# untitled.net
KiCad netlist of a schematic drawn in EAGLE
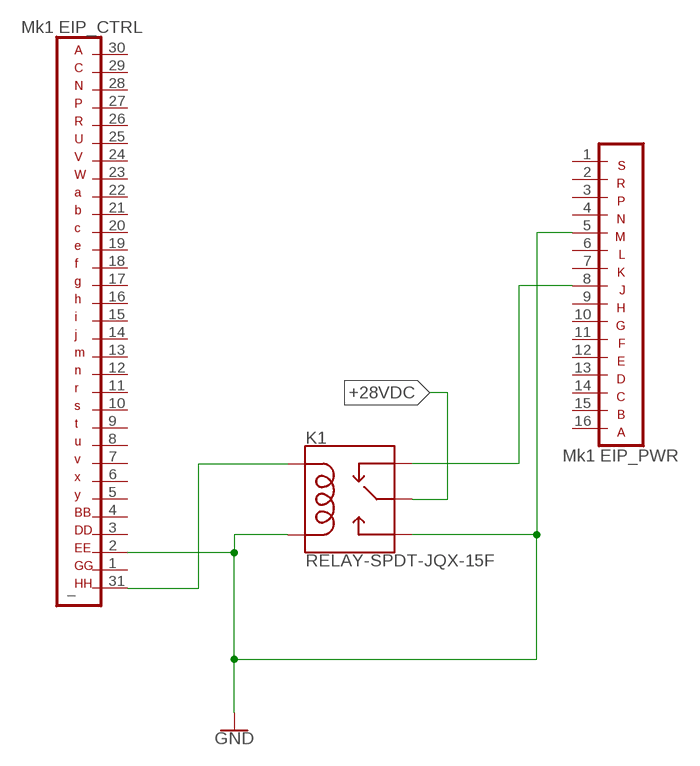
[diagram p0: schematic, sheet 1]

(export (version "E")
  (design (tool "Eeschema 10.0.6"))
  (components
    (comp (ref "J2")
      (value "SDGDSGG")
      (footprint "eagle-import:1X30")
      (libsource (lib "eagle-import") (part "SDGDSGG"))
    )
    (comp (ref "K1")
      (value "RELAY-SPDT-JQX-15F")
      (footprint "eagle-import:RELAY-T90")
      (libsource (lib "eagle-import") (part "RELAY-SPDT-JQX-15F"))
    )
    (comp (ref "U$1")
      (value "MK1_EIP_PWR")
      (footprint "eagle-import:1X16")
      (libsource (lib "eagle-import") (part "MK1_EIP_PWR"))
    )
  )
  (nets
    (net (code "1") (name "+28VDC") (class "Default")
      (node (ref "K1") (pin "MAIN") (pinfunction "MAIN_MAIN") (pintype "bidirectional"))
    )
    (net (code "2") (name "GND") (class "Default")
      (node (ref "J2") (pin "2") (pinfunction "2_2") (pintype "passive"))
      (node (ref "K1") (pin "COIL2") (pinfunction "COIL2_COIL2") (pintype "bidirectional"))
      (node (ref "K1") (pin "NO") (pinfunction "NO_NO") (pintype "bidirectional"))
      (node (ref "U$1") (pin "5") (pinfunction "5_5") (pintype "passive"))
    )
    (net (code "3") (name "Net-(J2-_)") (class "Default")
      (node (ref "J2") (pin "31") (pinfunction "__31") (pintype "passive"))
      (node (ref "K1") (pin "COIL1") (pinfunction "COIL1_COIL1") (pintype "bidirectional"))
    )
    (net (code "4") (name "Net-(K1-PadNC)") (class "Default")
      (node (ref "K1") (pin "NC") (pinfunction "NC_NC") (pintype "bidirectional"))
      (node (ref "U$1") (pin "8") (pinfunction "8_8") (pintype "passive"))
    )
    (net (code "5") (name "unconnected-(J2-Pad1)") (class "Default")
      (node (ref "J2") (pin "1") (pinfunction "1_1") (pintype "passive"))
    )
    (net (code "6") (name "unconnected-(J2-Pad3)") (class "Default")
      (node (ref "J2") (pin "3") (pinfunction "3_3") (pintype "passive"))
    )
    (net (code "7") (name "unconnected-(J2-Pad4)") (class "Default")
      (node (ref "J2") (pin "4") (pinfunction "4_4") (pintype "passive"))
    )
    (net (code "8") (name "unconnected-(J2-Pad5)") (class "Default")
      (node (ref "J2") (pin "5") (pinfunction "5_5") (pintype "passive"))
    )
    (net (code "9") (name "unconnected-(J2-Pad6)") (class "Default")
      (node (ref "J2") (pin "6") (pinfunction "6_6") (pintype "passive"))
    )
    (net (code "10") (name "unconnected-(J2-Pad7)") (class "Default")
      (node (ref "J2") (pin "7") (pinfunction "7_7") (pintype "passive"))
    )
    (net (code "11") (name "unconnected-(J2-Pad8)") (class "Default")
      (node (ref "J2") (pin "8") (pinfunction "8_8") (pintype "passive"))
    )
    (net (code "12") (name "unconnected-(J2-Pad9)") (class "Default")
      (node (ref "J2") (pin "9") (pinfunction "9_9") (pintype "passive"))
    )
    (net (code "13") (name "unconnected-(J2-Pad10)") (class "Default")
      (node (ref "J2") (pin "10") (pinfunction "10_10") (pintype "passive"))
    )
    (net (code "14") (name "unconnected-(J2-Pad11)") (class "Default")
      (node (ref "J2") (pin "11") (pinfunction "11_11") (pintype "passive"))
    )
    (net (code "15") (name "unconnected-(J2-Pad12)") (class "Default")
      (node (ref "J2") (pin "12") (pinfunction "12_12") (pintype "passive"))
    )
    (net (code "16") (name "unconnected-(J2-Pad13)") (class "Default")
      (node (ref "J2") (pin "13") (pinfunction "13_13") (pintype "passive"))
    )
    (net (code "17") (name "unconnected-(J2-Pad14)") (class "Default")
      (node (ref "J2") (pin "14") (pinfunction "14_14") (pintype "passive"))
    )
    (net (code "18") (name "unconnected-(J2-Pad15)") (class "Default")
      (node (ref "J2") (pin "15") (pinfunction "15_15") (pintype "passive"))
    )
    (net (code "19") (name "unconnected-(J2-Pad16)") (class "Default")
      (node (ref "J2") (pin "16") (pinfunction "16_16") (pintype "passive"))
    )
    (net (code "20") (name "unconnected-(J2-Pad17)") (class "Default")
      (node (ref "J2") (pin "17") (pinfunction "17_17") (pintype "passive"))
    )
    (net (code "21") (name "unconnected-(J2-Pad18)") (class "Default")
      (node (ref "J2") (pin "18") (pinfunction "18_18") (pintype "passive"))
    )
    (net (code "22") (name "unconnected-(J2-Pad19)") (class "Default")
      (node (ref "J2") (pin "19") (pinfunction "19_19") (pintype "passive"))
    )
    (net (code "23") (name "unconnected-(J2-Pad20)") (class "Default")
      (node (ref "J2") (pin "20") (pinfunction "20_20") (pintype "passive"))
    )
    (net (code "24") (name "unconnected-(J2-Pad21)") (class "Default")
      (node (ref "J2") (pin "21") (pinfunction "21_21") (pintype "passive"))
    )
    (net (code "25") (name "unconnected-(J2-Pad22)") (class "Default")
      (node (ref "J2") (pin "22") (pinfunction "22_22") (pintype "passive"))
    )
    (net (code "26") (name "unconnected-(J2-Pad23)") (class "Default")
      (node (ref "J2") (pin "23") (pinfunction "23_23") (pintype "passive"))
    )
    (net (code "27") (name "unconnected-(J2-Pad24)") (class "Default")
      (node (ref "J2") (pin "24") (pinfunction "24_24") (pintype "passive"))
    )
    (net (code "28") (name "unconnected-(J2-Pad25)") (class "Default")
      (node (ref "J2") (pin "25") (pinfunction "25_25") (pintype "passive"))
    )
    (net (code "29") (name "unconnected-(J2-Pad26)") (class "Default")
      (node (ref "J2") (pin "26") (pinfunction "26_26") (pintype "passive"))
    )
    (net (code "30") (name "unconnected-(J2-Pad27)") (class "Default")
      (node (ref "J2") (pin "27") (pinfunction "27_27") (pintype "passive"))
    )
    (net (code "31") (name "unconnected-(J2-Pad28)") (class "Default")
      (node (ref "J2") (pin "28") (pinfunction "28_28") (pintype "passive"))
    )
    (net (code "32") (name "unconnected-(J2-Pad29)") (class "Default")
      (node (ref "J2") (pin "29") (pinfunction "29_29") (pintype "passive"))
    )
    (net (code "33") (name "unconnected-(J2-Pad30)") (class "Default")
      (node (ref "J2") (pin "30") (pinfunction "30_30") (pintype "passive"))
    )
    (net (code "34") (name "unconnected-(U$1-Pad1)") (class "Default")
      (node (ref "U$1") (pin "1") (pinfunction "1_1") (pintype "passive"))
    )
    (net (code "35") (name "unconnected-(U$1-Pad2)") (class "Default")
      (node (ref "U$1") (pin "2") (pinfunction "2_2") (pintype "passive"))
    )
    (net (code "36") (name "unconnected-(U$1-Pad3)") (class "Default")
      (node (ref "U$1") (pin "3") (pinfunction "3_3") (pintype "passive"))
    )
    (net (code "37") (name "unconnected-(U$1-Pad4)") (class "Default")
      (node (ref "U$1") (pin "4") (pinfunction "4_4") (pintype "passive"))
    )
    (net (code "38") (name "unconnected-(U$1-Pad6)") (class "Default")
      (node (ref "U$1") (pin "6") (pinfunction "6_6") (pintype "passive"))
    )
    (net (code "39") (name "unconnected-(U$1-Pad7)") (class "Default")
      (node (ref "U$1") (pin "7") (pinfunction "7_7") (pintype "passive"))
    )
    (net (code "40") (name "unconnected-(U$1-Pad9)") (class "Default")
      (node (ref "U$1") (pin "9") (pinfunction "9_9") (pintype "passive"))
    )
    (net (code "41") (name "unconnected-(U$1-Pad10)") (class "Default")
      (node (ref "U$1") (pin "10") (pinfunction "10_10") (pintype "passive"))
    )
    (net (code "42") (name "unconnected-(U$1-Pad11)") (class "Default")
      (node (ref "U$1") (pin "11") (pinfunction "11_11") (pintype "passive"))
    )
    (net (code "43") (name "unconnected-(U$1-Pad12)") (class "Default")
      (node (ref "U$1") (pin "12") (pinfunction "12_12") (pintype "passive"))
    )
    (net (code "44") (name "unconnected-(U$1-Pad13)") (class "Default")
      (node (ref "U$1") (pin "13") (pinfunction "13_13") (pintype "passive"))
    )
    (net (code "45") (name "unconnected-(U$1-Pad14)") (class "Default")
      (node (ref "U$1") (pin "14") (pinfunction "14_14") (pintype "passive"))
    )
    (net (code "46") (name "unconnected-(U$1-Pad15)") (class "Default")
      (node (ref "U$1") (pin "15") (pinfunction "15_15") (pintype "passive"))
    )
    (net (code "47") (name "unconnected-(U$1-Pad16)") (class "Default")
      (node (ref "U$1") (pin "16") (pinfunction "16_16") (pintype "passive"))
    )
  )
)
